# toggleswitch_pump.net
KiCad netlist of a schematic drawn in EAGLE
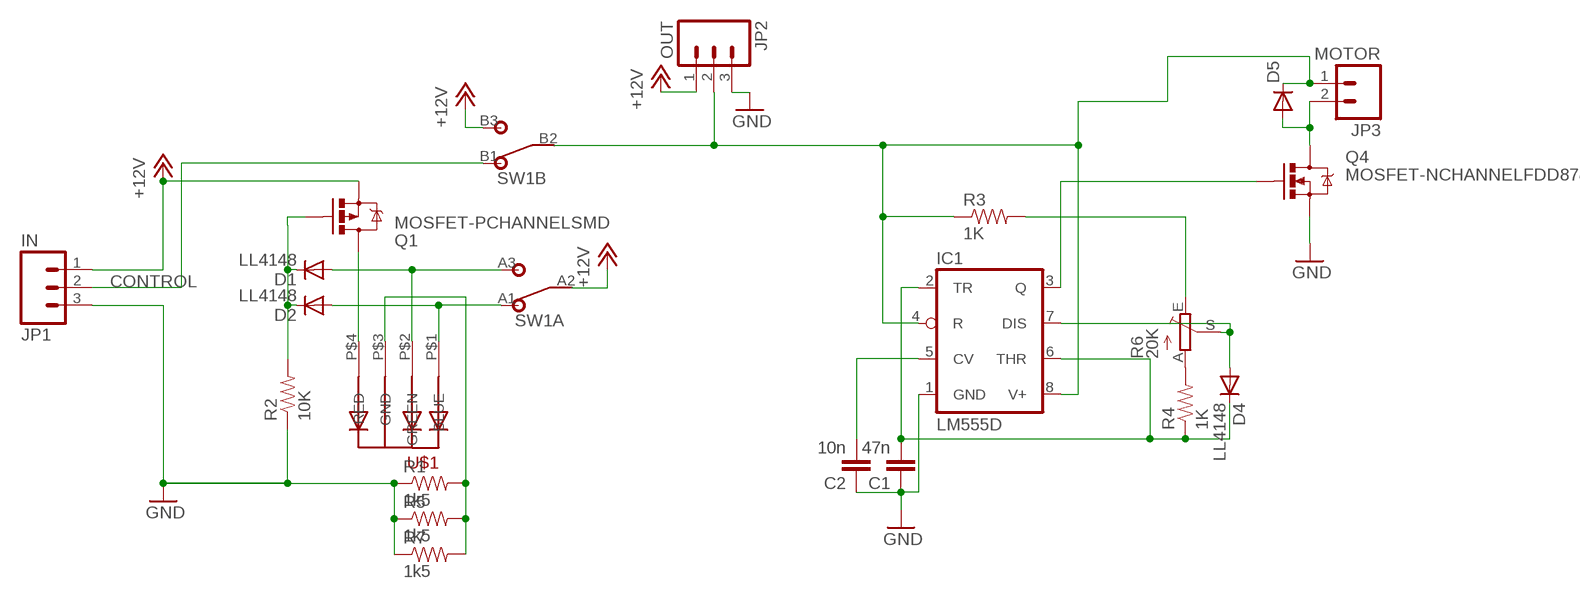
[diagram p0: schematic, sheet 1]

(export (version "E")
  (design (tool "Eeschema 10.0.6"))
  (components
    (comp (ref "C1")
      (value "47n")
      (footprint "eagle-import:0603-CAP")
      (libsource (lib "eagle-import") (part "CAP0603-CAP"))
    )
    (comp (ref "C2")
      (value "10n")
      (footprint "eagle-import:0603-CAP")
      (libsource (lib "eagle-import") (part "CAP0603-CAP"))
    )
    (comp (ref "D1")
      (value "LL4148")
      (footprint "eagle-import:MINIMELF")
      (libsource (lib "eagle-import") (part "DIODE-MINIMELF"))
    )
    (comp (ref "D2")
      (value "LL4148")
      (footprint "eagle-import:MINIMELF")
      (libsource (lib "eagle-import") (part "DIODE-MINIMELF"))
    )
    (comp (ref "D4")
      (value "LL4148")
      (footprint "eagle-import:MINIMELF")
      (libsource (lib "eagle-import") (part "DIODE-MINIMELF"))
    )
    (comp (ref "D5")
      (value "DIODESMB")
      (footprint "eagle-import:SMB-DIODE")
      (libsource (lib "eagle-import") (part "DIODESMB"))
    )
    (comp (ref "IC1")
      (value "LM555D")
      (footprint "eagle-import:SO08")
      (libsource (lib "eagle-import") (part "555DLM"))
    )
    (comp (ref "JP1")
      (value "IN")
      (footprint "eagle-import:MOLEX-1X3_LOCK")
      (libsource (lib "eagle-import") (part "M03POLAR_LOCK"))
    )
    (comp (ref "JP2")
      (value "OUT")
      (footprint "eagle-import:MOLEX-1X3_LOCK")
      (libsource (lib "eagle-import") (part "M03POLAR_LOCK"))
    )
    (comp (ref "JP3")
      (value "MOTOR")
      (footprint "eagle-import:MOLEX-1X2_LOCK")
      (libsource (lib "eagle-import") (part "M02POLAR_LOCK"))
    )
    (comp (ref "Q1")
      (value "MOSFET-PCHANNELSMD")
      (footprint "eagle-import:SOT23-3")
      (libsource (lib "eagle-import") (part "MOSFET-PCHANNELSMD"))
    )
    (comp (ref "Q4")
      (value "MOSFET-NCHANNELFDD8780")
      (footprint "eagle-import:DPAK")
      (libsource (lib "eagle-import") (part "MOSFET-NCHANNELFDD8780"))
    )
    (comp (ref "R1")
      (value "1k5")
      (footprint "eagle-import:0603-RES")
      (libsource (lib "eagle-import") (part "RESISTOR0603-RES"))
    )
    (comp (ref "R2")
      (value "10K")
      (footprint "eagle-import:0603-RES")
      (libsource (lib "eagle-import") (part "RESISTOR0603-RES"))
    )
    (comp (ref "R3")
      (value "1K")
      (footprint "eagle-import:0603-RES")
      (libsource (lib "eagle-import") (part "RESISTOR0603-RES"))
    )
    (comp (ref "R4")
      (value "1K")
      (footprint "eagle-import:0603-RES")
      (libsource (lib "eagle-import") (part "RESISTOR0603-RES"))
    )
    (comp (ref "R5")
      (value "1k5")
      (footprint "eagle-import:0603-RES")
      (libsource (lib "eagle-import") (part "RESISTOR0603-RES"))
    )
    (comp (ref "R6")
      (value "20K")
      (footprint "eagle-import:RJ9W")
      (libsource (lib "eagle-import") (part "TRIM_EU-RJ9W"))
    )
    (comp (ref "R7")
      (value "1k5")
      (footprint "eagle-import:0603-RES")
      (libsource (lib "eagle-import") (part "RESISTOR0603-RES"))
    )
    (comp (ref "SW1")
      (value "DPDT")
      (footprint "eagle-import:DPDT")
      (libsource (lib "eagle-import") (part "DPDT"))
    )
    (comp (ref "U$1")
      (value "5MMRGBLED")
      (footprint "eagle-import:LED5MMRGB")
      (libsource (lib "eagle-import") (part "5MMRGBLED"))
    )
  )
  (nets
    (net (code "1") (name "+12V") (class "Default")
      (node (ref "JP1") (pin "1") (pinfunction "1_1") (pintype "passive"))
      (node (ref "JP2") (pin "1") (pinfunction "1_1") (pintype "passive"))
      (node (ref "Q1") (pin "2") (pinfunction "S_2") (pintype "passive"))
      (node (ref "SW1") (pin "A2") (pinfunction "2_A2") (pintype "passive"))
      (node (ref "SW1") (pin "B3") (pinfunction "3_B3") (pintype "passive"))
    )
    (net (code "2") (name "/CONTROL") (class "Default")
      (node (ref "JP1") (pin "2") (pinfunction "2_2") (pintype "passive"))
      (node (ref "SW1") (pin "B1") (pinfunction "1_B1") (pintype "passive"))
    )
    (net (code "3") (name "GND") (class "Default")
      (node (ref "C1") (pin "1") (pinfunction "1_1") (pintype "passive"))
      (node (ref "C2") (pin "1") (pinfunction "1_1") (pintype "passive"))
      (node (ref "IC1") (pin "1") (pinfunction "GND_1") (pintype "power_in"))
      (node (ref "JP1") (pin "3") (pinfunction "3_3") (pintype "passive"))
      (node (ref "JP2") (pin "3") (pinfunction "3_3") (pintype "passive"))
      (node (ref "Q4") (pin "3") (pinfunction "S_3") (pintype "passive"))
      (node (ref "R1") (pin "1") (pinfunction "1_1") (pintype "passive"))
      (node (ref "R2") (pin "1") (pinfunction "1_1") (pintype "passive"))
      (node (ref "R5") (pin "1") (pinfunction "1_1") (pintype "passive"))
      (node (ref "R7") (pin "1") (pinfunction "1_1") (pintype "passive"))
    )
    (net (code "4") (name "Net-(IC1-CV)") (class "Default")
      (node (ref "C2") (pin "2") (pinfunction "2_2") (pintype "passive"))
      (node (ref "IC1") (pin "5") (pinfunction "CV_5") (pintype "input"))
    )
    (net (code "5") (name "Net-(IC1-DIS)") (class "Default")
      (node (ref "D4") (pin "A") (pinfunction "A_A") (pintype "passive"))
      (node (ref "IC1") (pin "7") (pinfunction "DIS_7") (pintype "input"))
      (node (ref "R6") (pin "S") (pinfunction "S_S") (pintype "passive"))
    )
    (net (code "6") (name "Net-(IC1-Q)") (class "Default")
      (node (ref "IC1") (pin "3") (pinfunction "Q_3") (pintype "output"))
      (node (ref "Q4") (pin "1") (pinfunction "G_1") (pintype "passive"))
    )
    (net (code "7") (name "Net-(IC1-R)") (class "Default")
      (node (ref "D5") (pin "C") (pinfunction "C_C") (pintype "passive"))
      (node (ref "IC1") (pin "4") (pinfunction "R_4") (pintype "input"))
      (node (ref "IC1") (pin "8") (pinfunction "V+_8") (pintype "power_in"))
      (node (ref "JP2") (pin "2") (pinfunction "2_2") (pintype "passive"))
      (node (ref "JP3") (pin "1") (pinfunction "1_1") (pintype "passive"))
      (node (ref "R3") (pin "1") (pinfunction "1_1") (pintype "passive"))
      (node (ref "SW1") (pin "B2") (pinfunction "2_B2") (pintype "passive"))
    )
    (net (code "8") (name "Net-(IC1-THR)") (class "Default")
      (node (ref "C1") (pin "2") (pinfunction "2_2") (pintype "passive"))
      (node (ref "D4") (pin "C") (pinfunction "C_C") (pintype "passive"))
      (node (ref "IC1") (pin "2") (pinfunction "TR_2") (pintype "input"))
      (node (ref "IC1") (pin "6") (pinfunction "THR_6") (pintype "input"))
      (node (ref "R4") (pin "1") (pinfunction "1_1") (pintype "passive"))
    )
    (net (code "9") (name "Net-(Q1-D)") (class "Default")
      (node (ref "Q1") (pin "3") (pinfunction "D_3") (pintype "passive"))
      (node (ref "U$1") (pin "P$4") (pinfunction "RED_P$4") (pintype "bidirectional"))
    )
    (net (code "10") (name "Net-(Q1-G)") (class "Default")
      (node (ref "D1") (pin "C") (pinfunction "C_C") (pintype "passive"))
      (node (ref "D2") (pin "C") (pinfunction "C_C") (pintype "passive"))
      (node (ref "Q1") (pin "1") (pinfunction "G_1") (pintype "passive"))
      (node (ref "R2") (pin "2") (pinfunction "2_2") (pintype "passive"))
    )
    (net (code "11") (name "Net-(Q4-D)") (class "Default")
      (node (ref "D5") (pin "A") (pinfunction "A_A") (pintype "passive"))
      (node (ref "JP3") (pin "2") (pinfunction "2_2") (pintype "passive"))
      (node (ref "Q4") (pin "4") (pinfunction "D_4") (pintype "passive"))
    )
    (net (code "12") (name "Net-(R3-Pad2)") (class "Default")
      (node (ref "R3") (pin "2") (pinfunction "2_2") (pintype "passive"))
      (node (ref "R6") (pin "E") (pinfunction "E_E") (pintype "passive"))
    )
    (net (code "13") (name "Net-(R4-Pad2)") (class "Default")
      (node (ref "R4") (pin "2") (pinfunction "2_2") (pintype "passive"))
      (node (ref "R6") (pin "A") (pinfunction "A_A") (pintype "passive"))
    )
    (net (code "14") (name "Net-(SW1A-1)") (class "Default")
      (node (ref "D2") (pin "A") (pinfunction "A_A") (pintype "passive"))
      (node (ref "SW1") (pin "A1") (pinfunction "1_A1") (pintype "passive"))
      (node (ref "U$1") (pin "P$1") (pinfunction "BLUE_P$1") (pintype "bidirectional"))
    )
    (net (code "15") (name "Net-(SW1A-3)") (class "Default")
      (node (ref "D1") (pin "A") (pinfunction "A_A") (pintype "passive"))
      (node (ref "SW1") (pin "A3") (pinfunction "3_A3") (pintype "passive"))
      (node (ref "U$1") (pin "P$2") (pinfunction "GREEN_P$2") (pintype "bidirectional"))
    )
    (net (code "16") (name "Net-(U$1-GND)") (class "Default")
      (node (ref "R1") (pin "2") (pinfunction "2_2") (pintype "passive"))
      (node (ref "R5") (pin "2") (pinfunction "2_2") (pintype "passive"))
      (node (ref "R7") (pin "2") (pinfunction "2_2") (pintype "passive"))
      (node (ref "U$1") (pin "P$3") (pinfunction "GND_P$3") (pintype "bidirectional"))
    )
  )
)
